# BAM_SIMPLE_1U_6HP.net
KiCad netlist of a schematic drawn in EAGLE
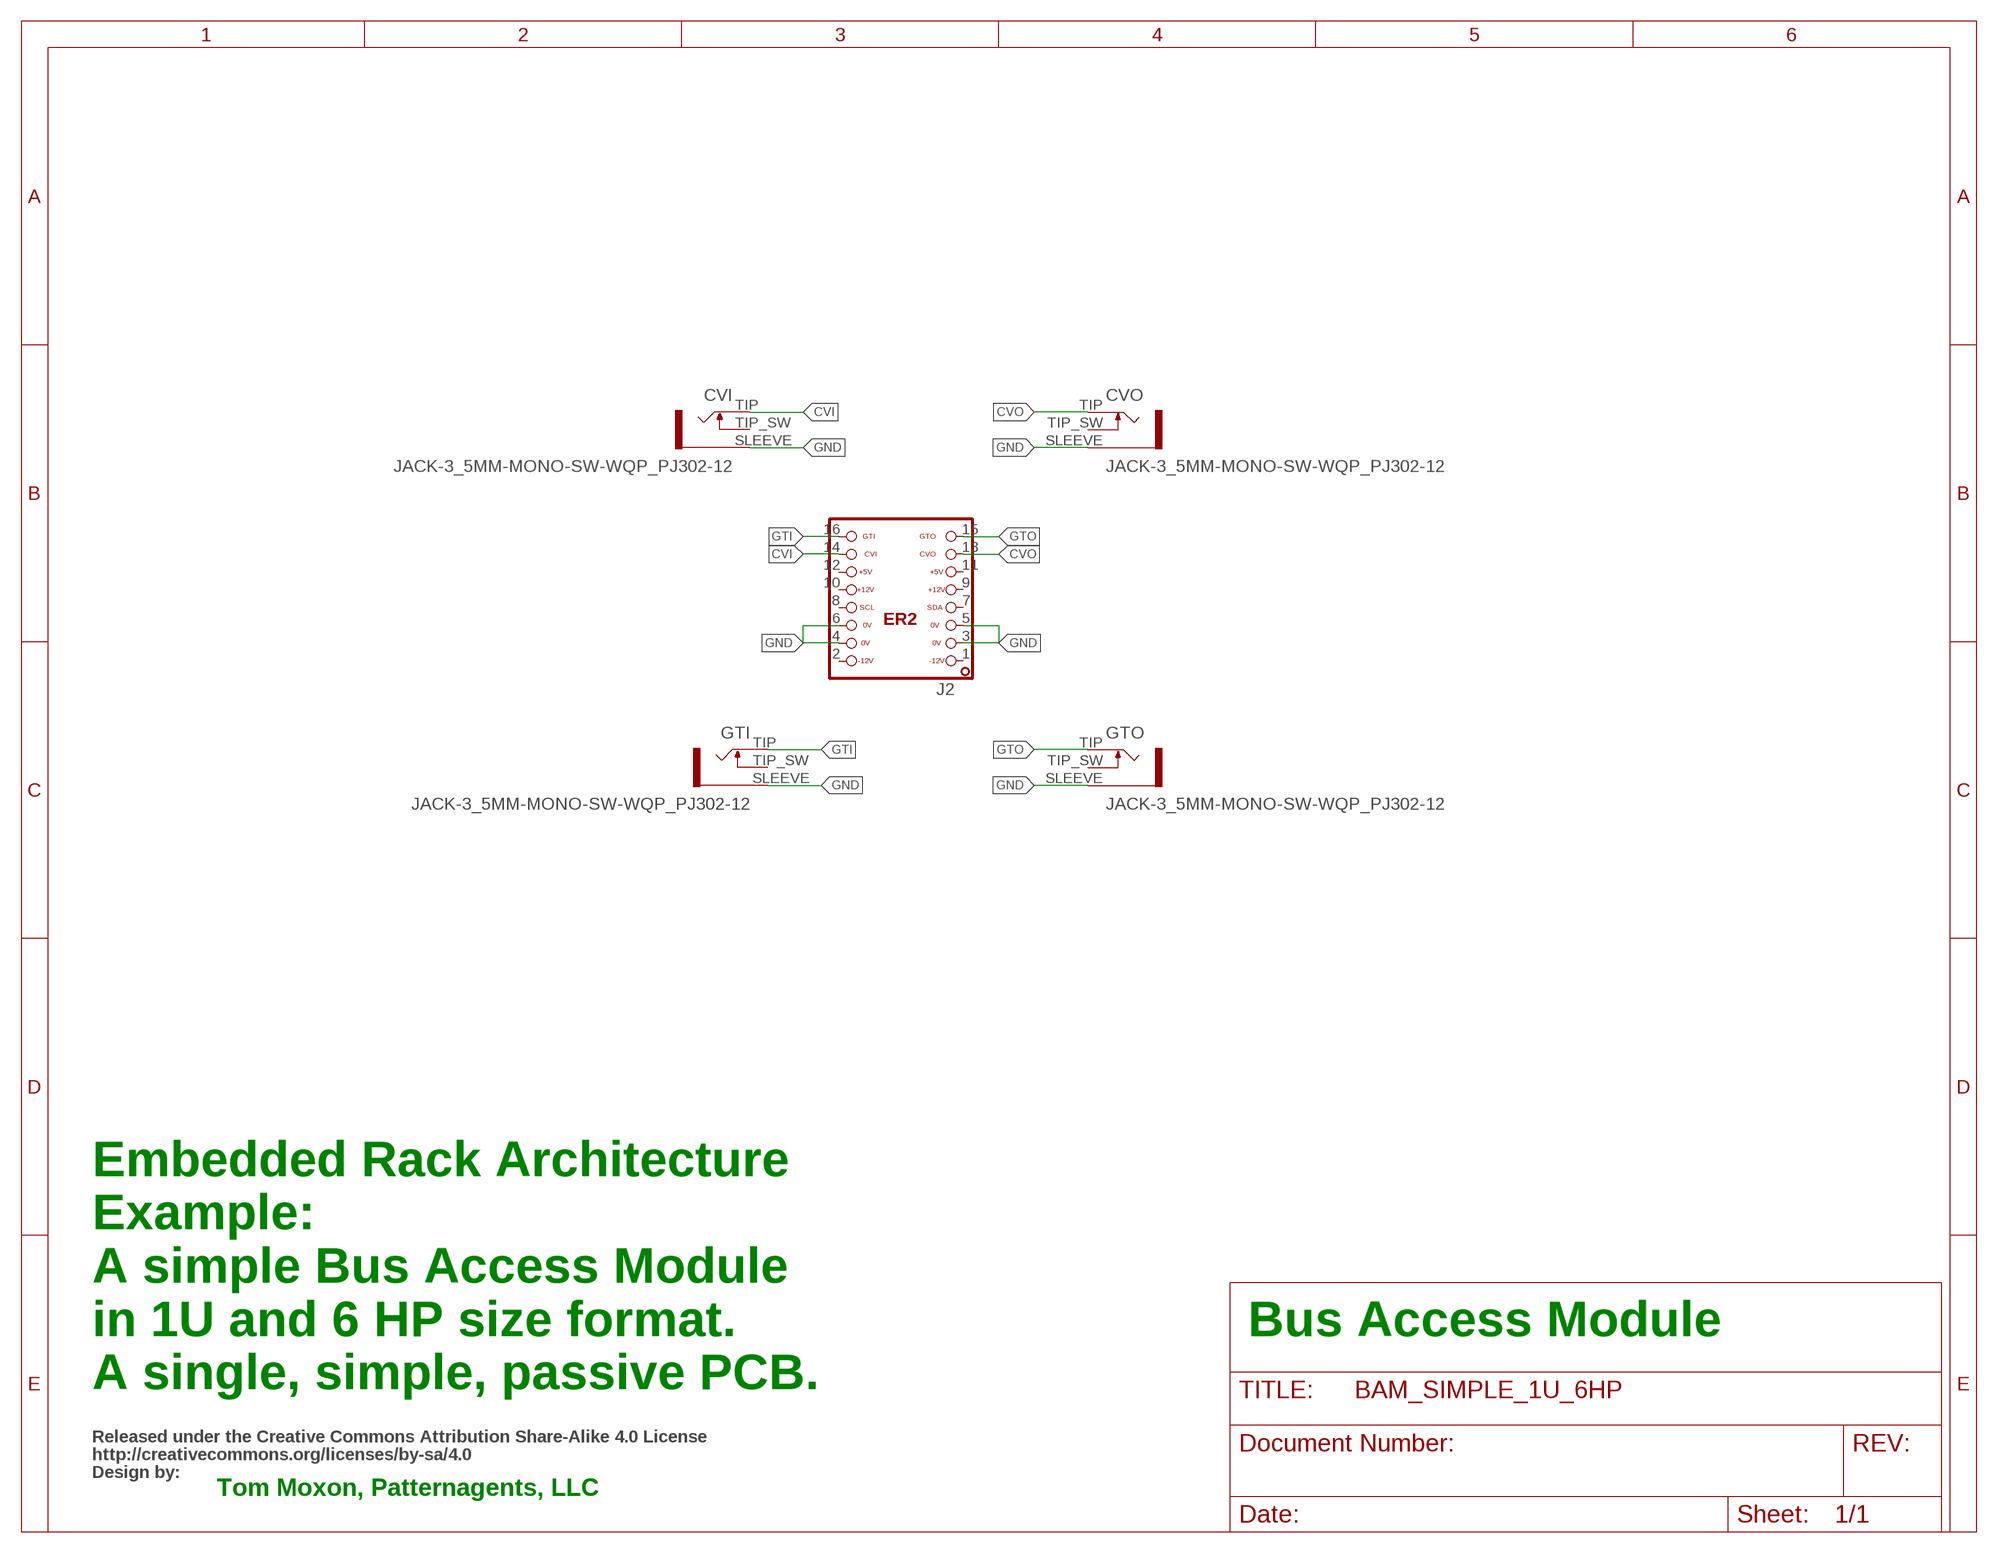
[diagram p0: schematic, sheet 1]

(export (version "E")
  (design (tool "Eeschema 10.0.6"))
  (components
    (comp (ref "CVI")
      (value "JACK-3_5MM-MONO-SW-WQP_PJ302-12")
      (footprint "eagle-import:WQP_PJ301M-12")
      (libsource (lib "eagle-import") (part "JACK-3_5MM-MONO-SW-WQP_PJ302-12"))
    )
    (comp (ref "CVO")
      (value "JACK-3_5MM-MONO-SW-WQP_PJ302-12")
      (footprint "eagle-import:WQP_PJ301M-12")
      (libsource (lib "eagle-import") (part "JACK-3_5MM-MONO-SW-WQP_PJ302-12"))
    )
    (comp (ref "GTI")
      (value "JACK-3_5MM-MONO-SW-WQP_PJ302-12")
      (footprint "eagle-import:WQP_PJ301M-12")
      (libsource (lib "eagle-import") (part "JACK-3_5MM-MONO-SW-WQP_PJ302-12"))
    )
    (comp (ref "GTO")
      (value "JACK-3_5MM-MONO-SW-WQP_PJ302-12")
      (footprint "eagle-import:WQP_PJ301M-12")
      (libsource (lib "eagle-import") (part "JACK-3_5MM-MONO-SW-WQP_PJ302-12"))
    )
    (comp (ref "J2")
      (value "ER2-SHROUD")
      (footprint "eagle-import:ER2")
      (libsource (lib "eagle-import") (part "ER2-SHROUD"))
    )
    (comp (ref "TOMMOXON")
      (value "BY_CC_SA_TEXTNULL")
      (footprint "eagle-import:NULL_SYM")
      (libsource (lib "eagle-import") (part "BY_CC_SA_TEXTNULL"))
    )
  )
  (nets
    (net (code "1") (name "CVI") (class "Default")
      (node (ref "CVI") (pin "TIP") (pinfunction "TIP_TIP") (pintype "passive"))
      (node (ref "J2") (pin "14") (pinfunction "14_14") (pintype "passive"))
    )
    (net (code "2") (name "CVO") (class "Default")
      (node (ref "CVO") (pin "TIP") (pinfunction "TIP_TIP") (pintype "passive"))
      (node (ref "J2") (pin "13") (pinfunction "13_13") (pintype "passive"))
    )
    (net (code "3") (name "GND") (class "Default")
      (node (ref "CVI") (pin "SLEEVE") (pinfunction "SLEEVE_SLEEVE") (pintype "passive"))
      (node (ref "CVO") (pin "SLEEVE") (pinfunction "SLEEVE_SLEEVE") (pintype "passive"))
      (node (ref "GTI") (pin "SLEEVE") (pinfunction "SLEEVE_SLEEVE") (pintype "passive"))
      (node (ref "GTO") (pin "SLEEVE") (pinfunction "SLEEVE_SLEEVE") (pintype "passive"))
      (node (ref "J2") (pin "3") (pinfunction "3_3") (pintype "passive"))
      (node (ref "J2") (pin "4") (pinfunction "4_4") (pintype "passive"))
      (node (ref "J2") (pin "5") (pinfunction "5_5") (pintype "passive"))
      (node (ref "J2") (pin "6") (pinfunction "6_6") (pintype "passive"))
    )
    (net (code "4") (name "GTI") (class "Default")
      (node (ref "GTI") (pin "TIP") (pinfunction "TIP_TIP") (pintype "passive"))
      (node (ref "J2") (pin "16") (pinfunction "16_16") (pintype "passive"))
    )
    (net (code "5") (name "GTO") (class "Default")
      (node (ref "GTO") (pin "TIP") (pinfunction "TIP_TIP") (pintype "passive"))
      (node (ref "J2") (pin "15") (pinfunction "15_15") (pintype "passive"))
    )
    (net (code "6") (name "unconnected-(CVI-PadTIP_SW)") (class "Default")
      (node (ref "CVI") (pin "TIP_SW") (pinfunction "TIP_SW_TIP_SW") (pintype "passive"))
    )
    (net (code "7") (name "unconnected-(CVO-PadTIP_SW)") (class "Default")
      (node (ref "CVO") (pin "TIP_SW") (pinfunction "TIP_SW_TIP_SW") (pintype "passive"))
    )
    (net (code "8") (name "unconnected-(GTI-PadTIP_SW)") (class "Default")
      (node (ref "GTI") (pin "TIP_SW") (pinfunction "TIP_SW_TIP_SW") (pintype "passive"))
    )
    (net (code "9") (name "unconnected-(GTO-PadTIP_SW)") (class "Default")
      (node (ref "GTO") (pin "TIP_SW") (pinfunction "TIP_SW_TIP_SW") (pintype "passive"))
    )
    (net (code "10") (name "unconnected-(J2-Pad1)") (class "Default")
      (node (ref "J2") (pin "1") (pinfunction "1_1") (pintype "passive"))
    )
    (net (code "11") (name "unconnected-(J2-Pad2)") (class "Default")
      (node (ref "J2") (pin "2") (pinfunction "2_2") (pintype "passive"))
    )
    (net (code "12") (name "unconnected-(J2-Pad7)") (class "Default")
      (node (ref "J2") (pin "7") (pinfunction "7_7") (pintype "passive"))
    )
    (net (code "13") (name "unconnected-(J2-Pad8)") (class "Default")
      (node (ref "J2") (pin "8") (pinfunction "8_8") (pintype "passive"))
    )
    (net (code "14") (name "unconnected-(J2-Pad9)") (class "Default")
      (node (ref "J2") (pin "9") (pinfunction "9_9") (pintype "passive"))
    )
    (net (code "15") (name "unconnected-(J2-Pad10)") (class "Default")
      (node (ref "J2") (pin "10") (pinfunction "10_10") (pintype "passive"))
    )
    (net (code "16") (name "unconnected-(J2-Pad11)") (class "Default")
      (node (ref "J2") (pin "11") (pinfunction "11_11") (pintype "passive"))
    )
    (net (code "17") (name "unconnected-(J2-Pad12)") (class "Default")
      (node (ref "J2") (pin "12") (pinfunction "12_12") (pintype "passive"))
    )
  )
)
